# RMP_-_FBPS_MOBO_0_0_1.net
KiCad netlist of a schematic drawn in EAGLE
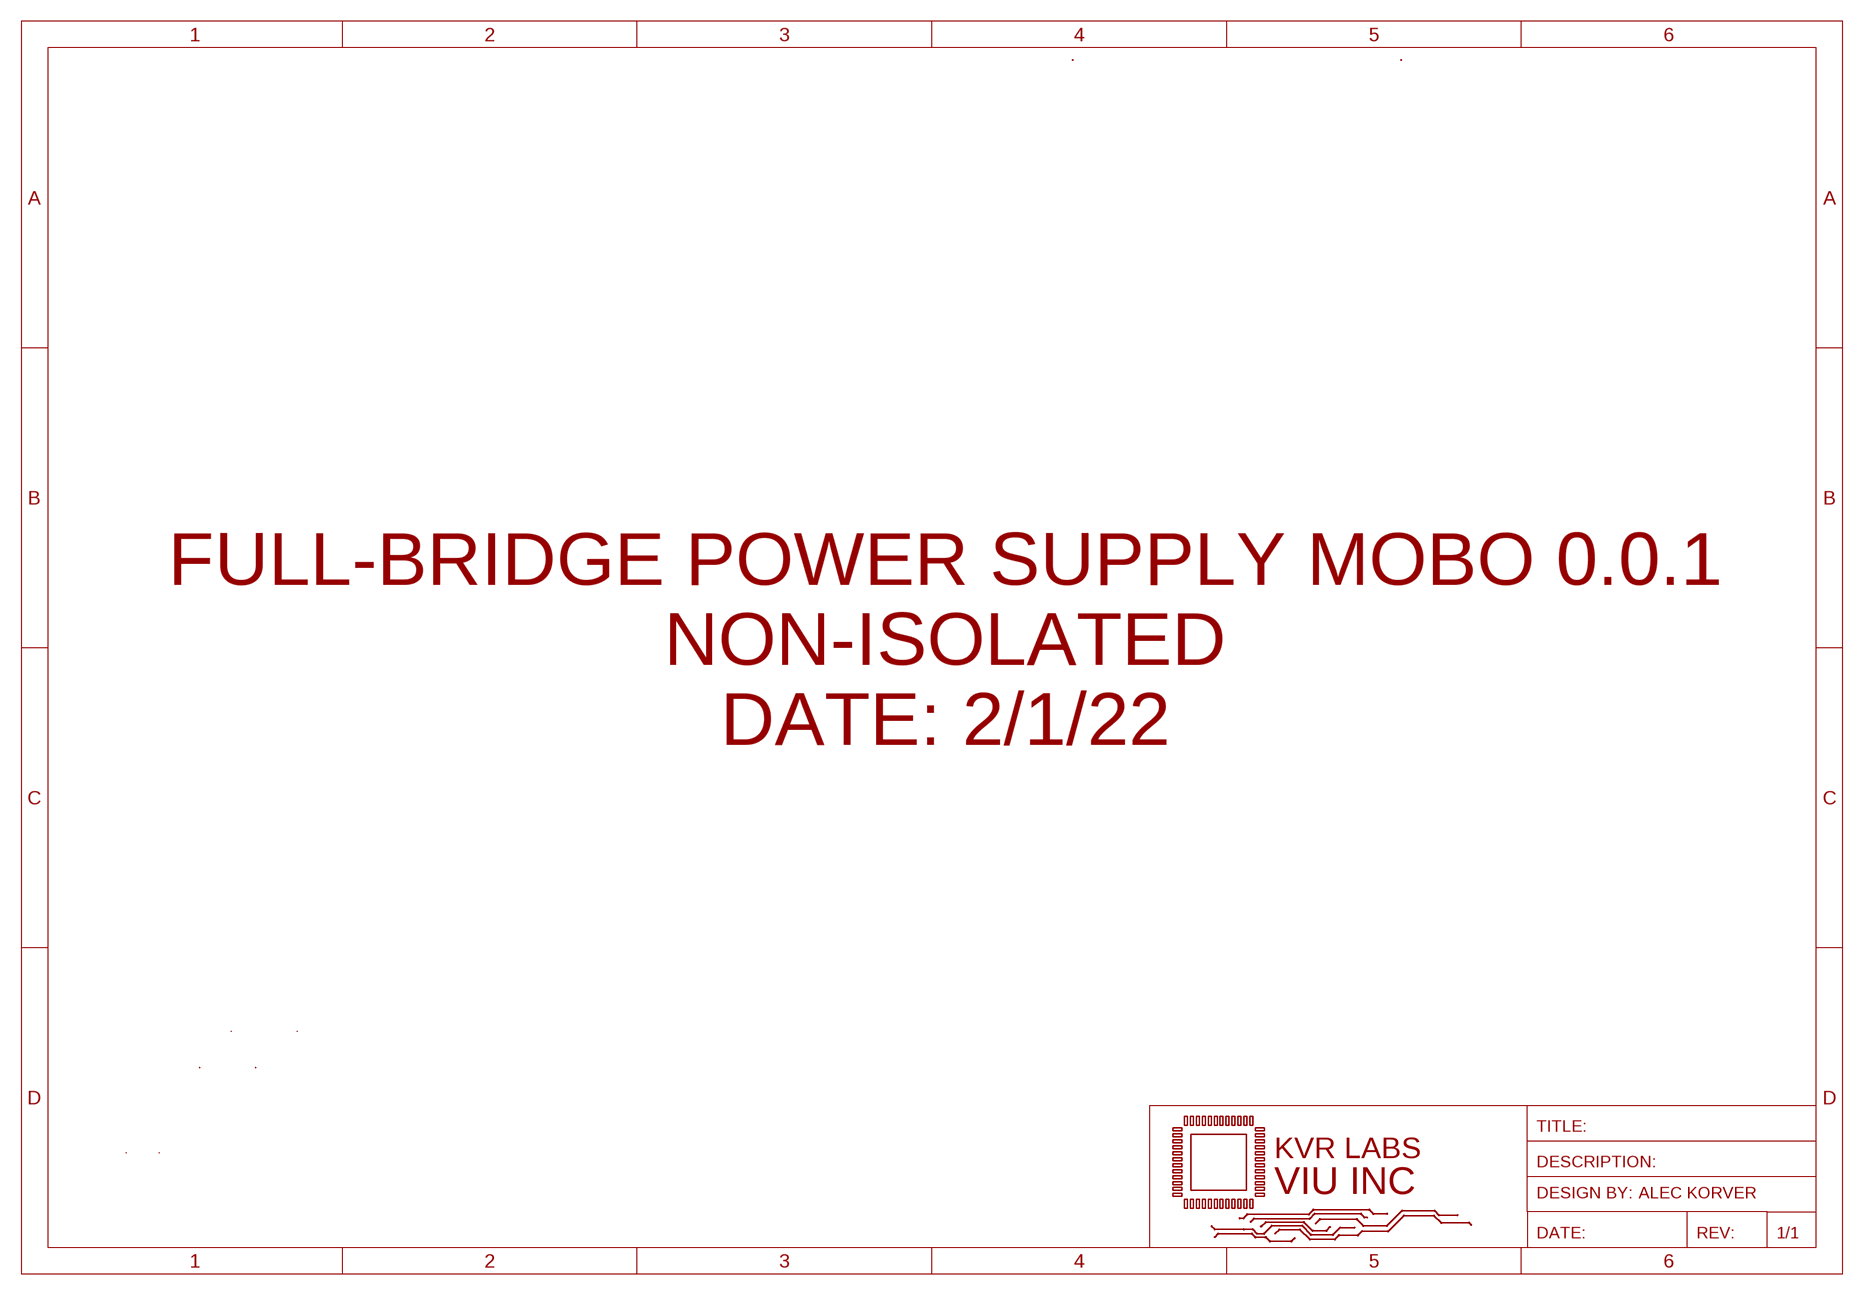
[diagram p0: schematic, sheet 1]
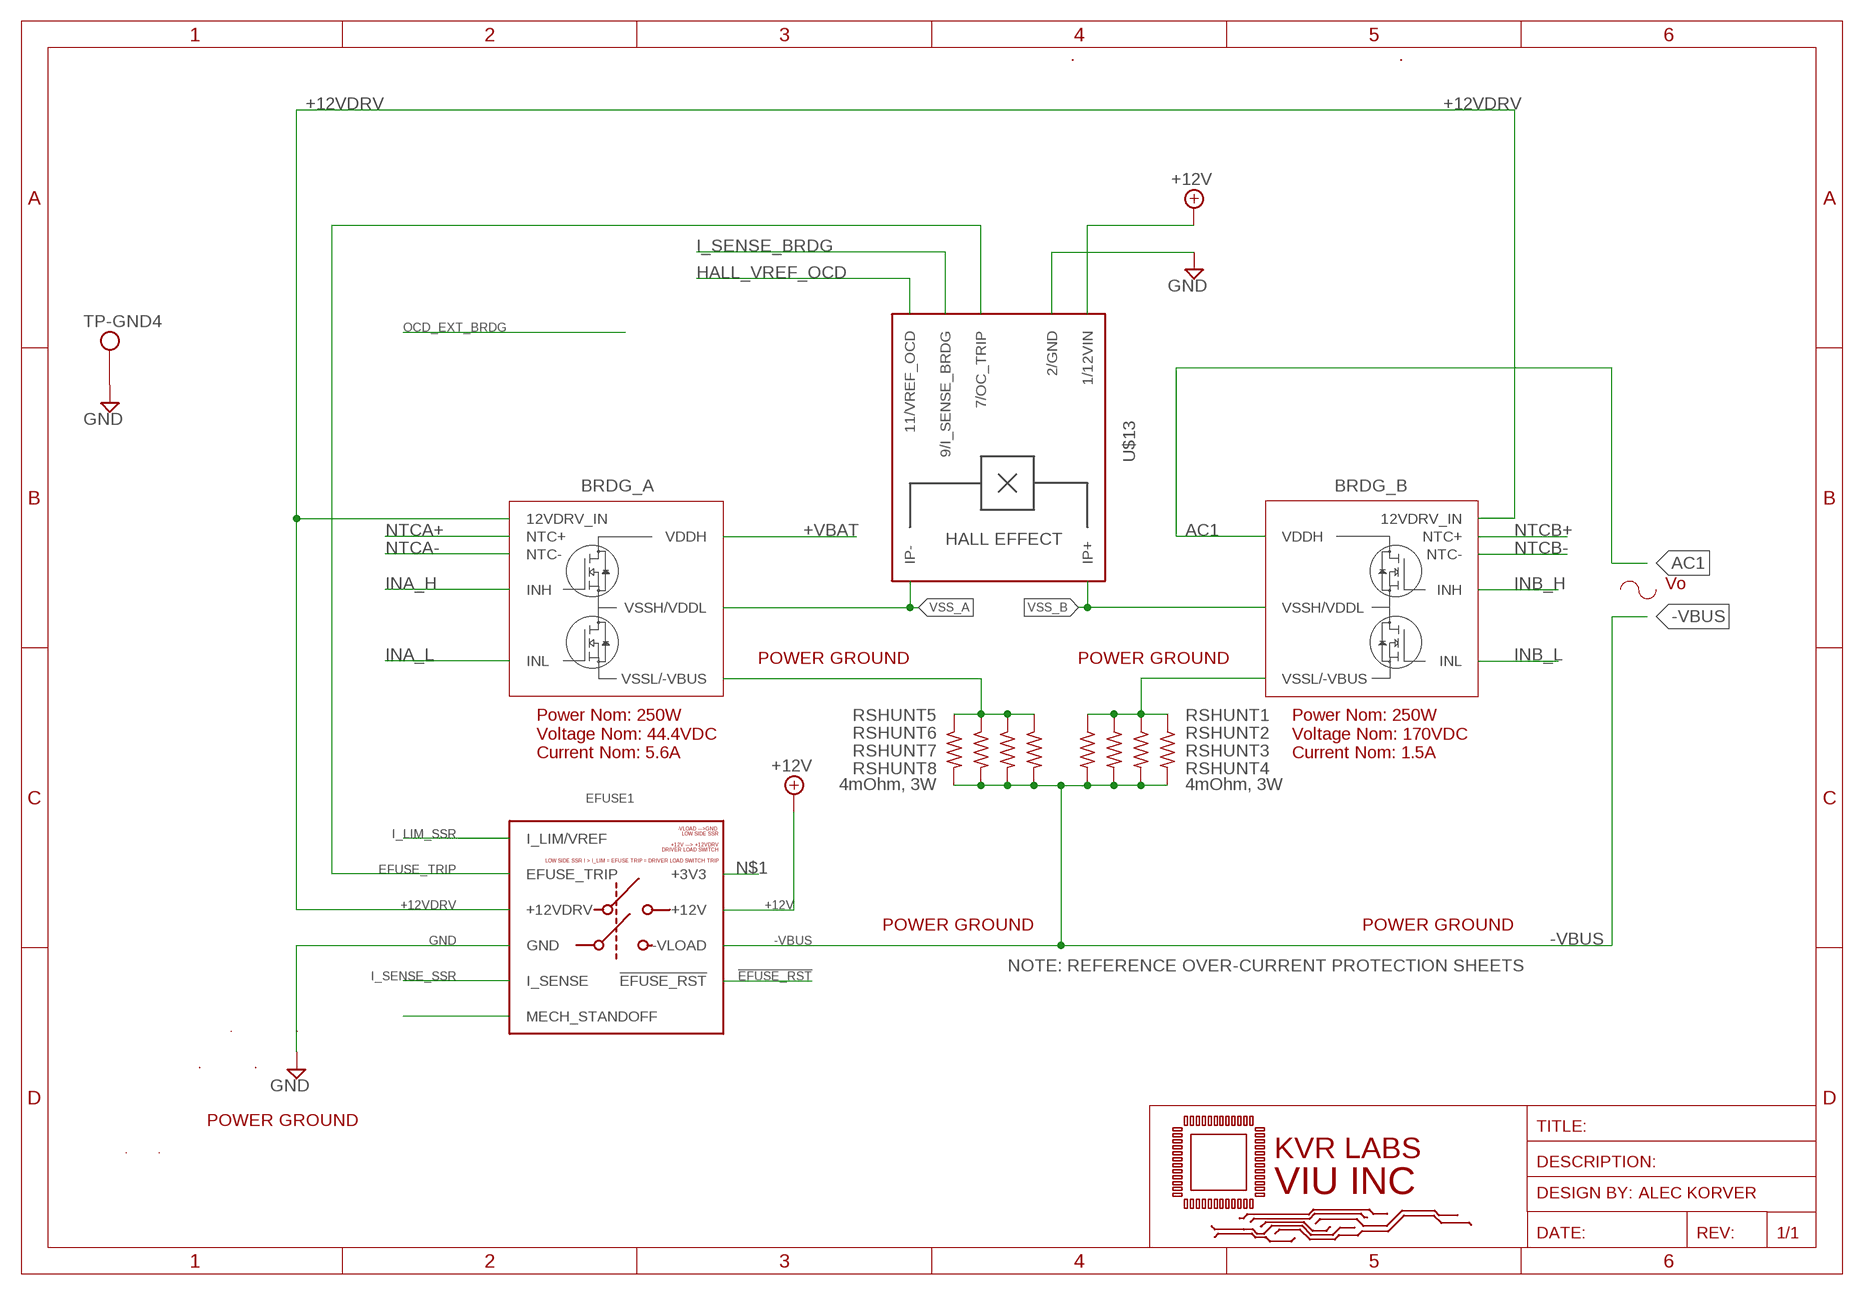
[diagram p1: schematic, sheet 2]
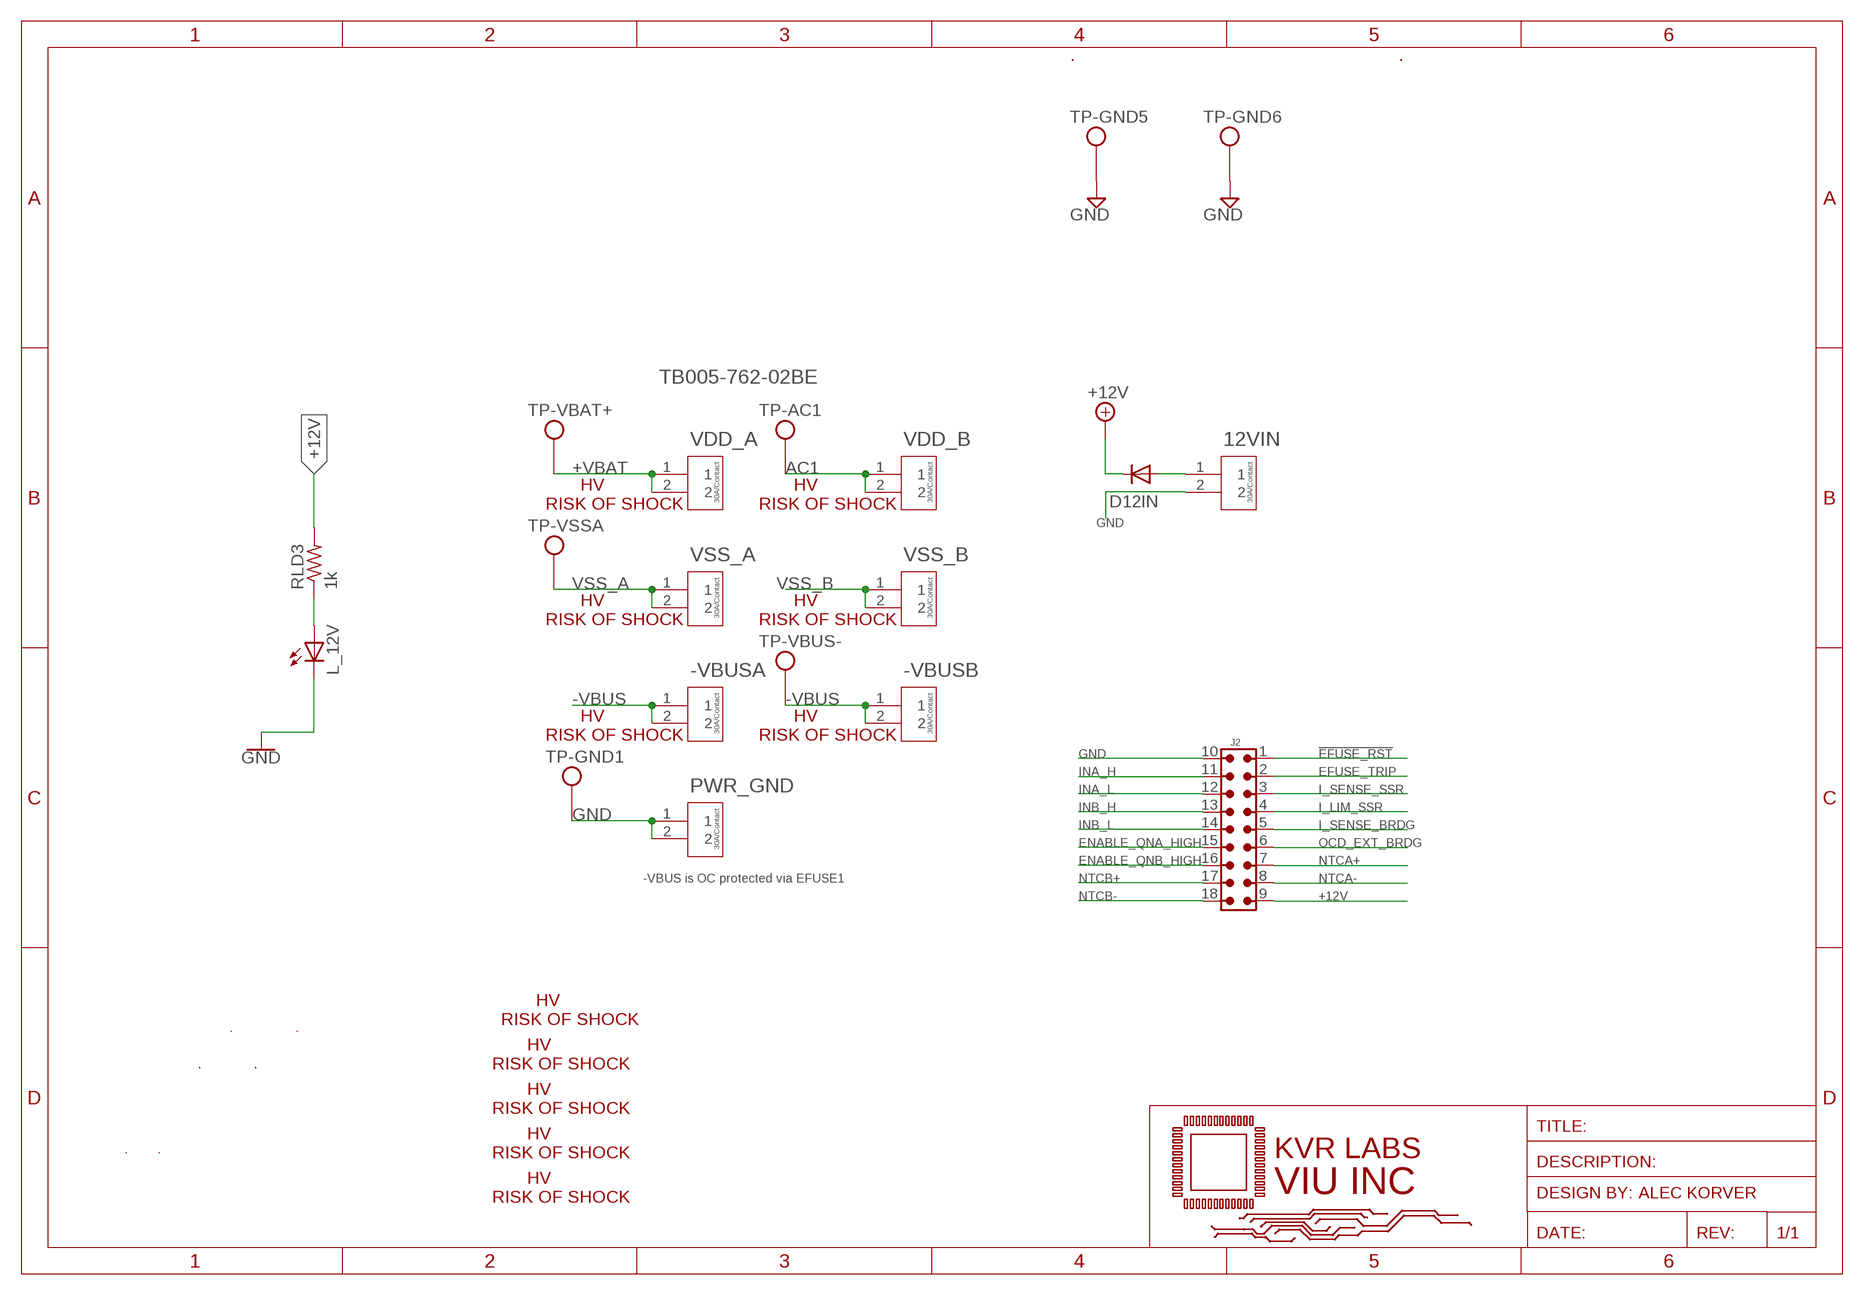
[diagram p2: schematic, sheet 3]
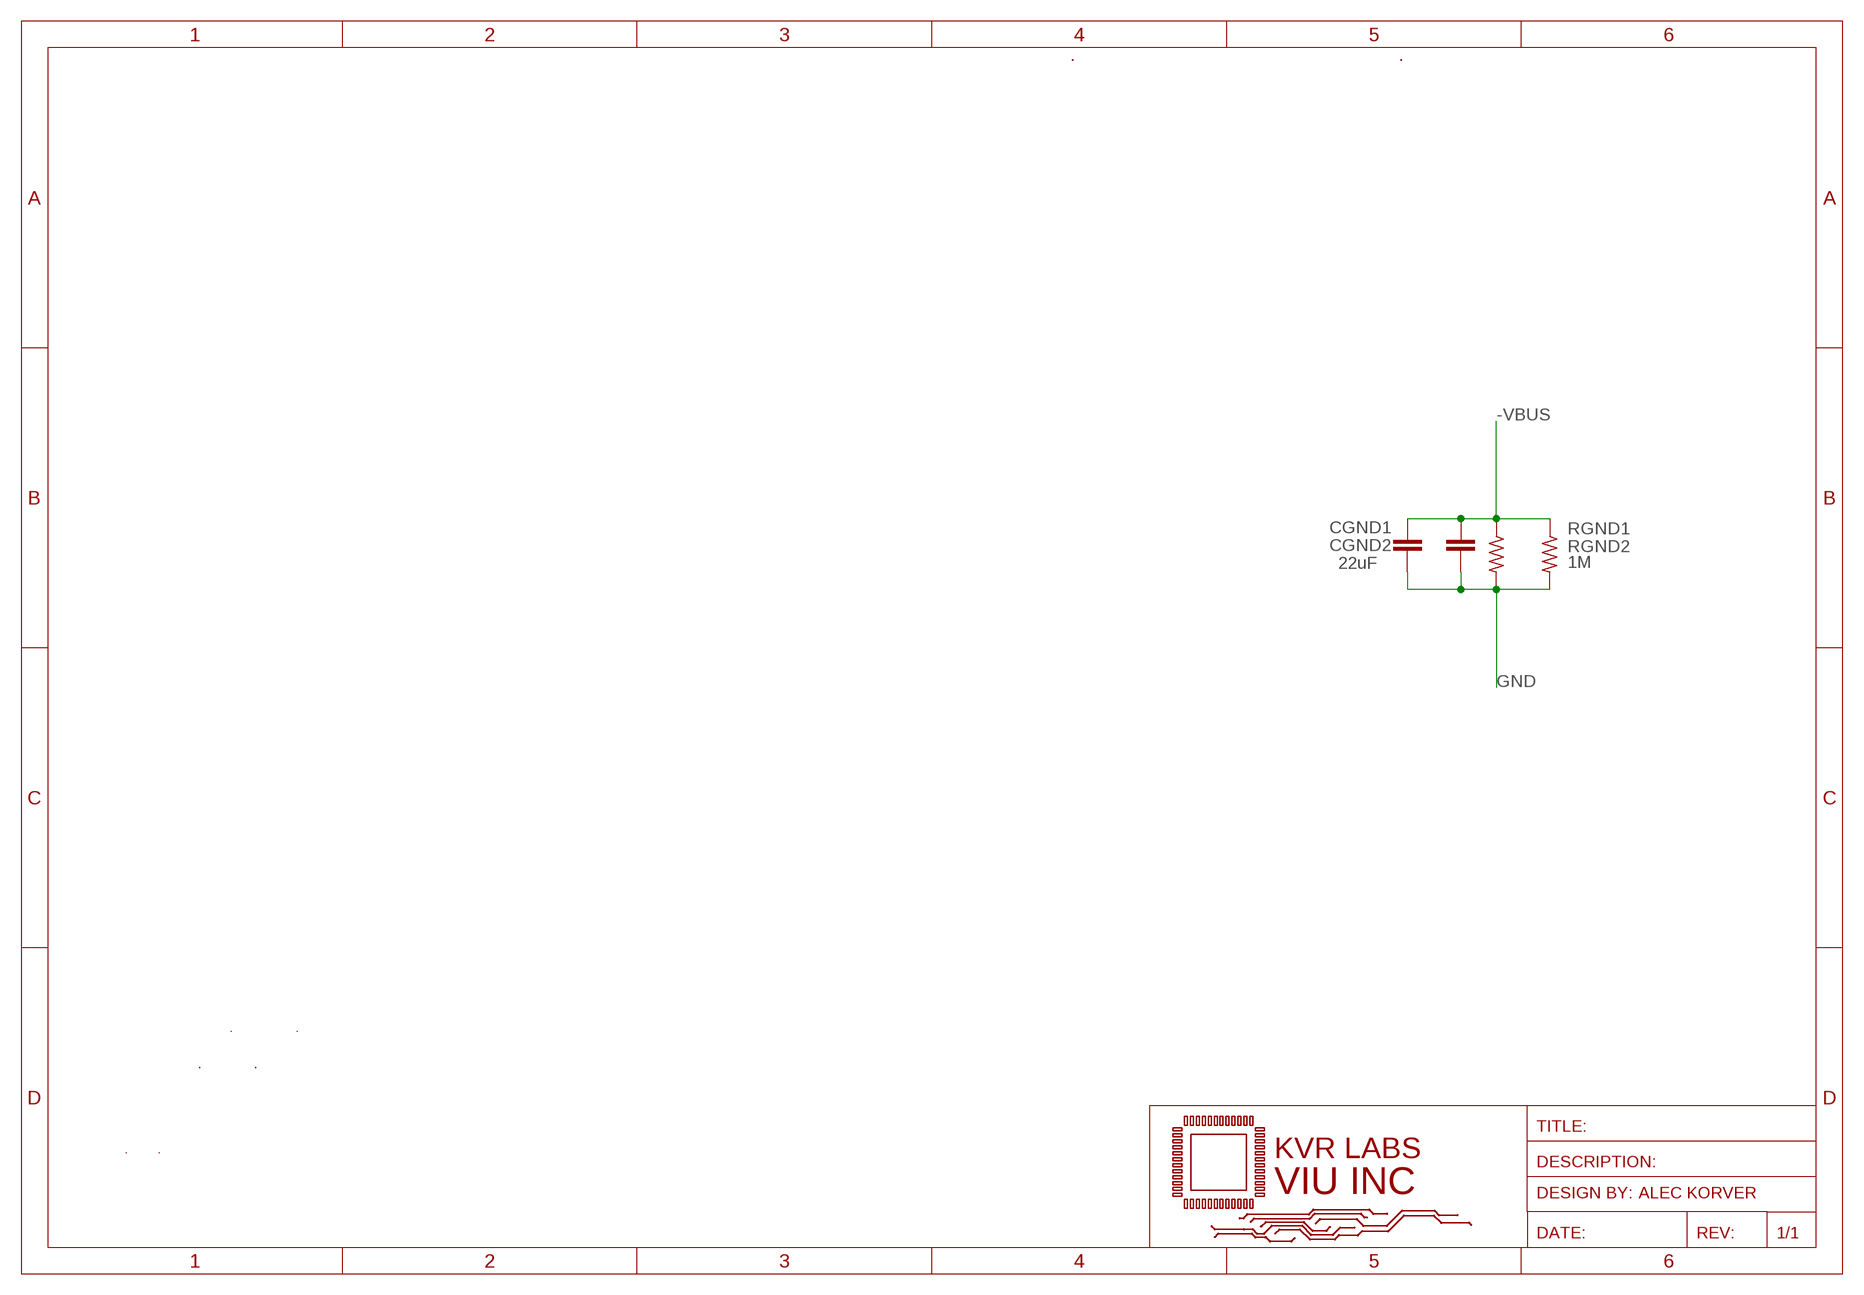
[diagram p3: schematic, sheet 4]

(export (version "E")
  (design (tool "Eeschema 10.0.6"))
  (components
    (comp (ref "BRDG_A")
      (value "1/2BRIDGE")
      (footprint "eagle-import:1_2BRIDGE")
      (fields (field (name "LCSC_PART") "DNP/CUSTOM"))
      (libsource (lib "eagle-import") (part "1/2BRIDGE"))
    )
    (comp (ref "BRDG_B")
      (value "1/2BRIDGE")
      (footprint "eagle-import:1_2BRIDGE")
      (fields (field (name "LCSC_PART") "DNP/CUSTOM"))
      (libsource (lib "eagle-import") (part "1/2BRIDGE"))
    )
    (comp (ref "EFUSE1")
      (value "EFUSE_2.0.0")
      (footprint "eagle-import:EFUSE_2.0.0")
      (fields (field (name "LCSC_PART") "DNP/CUSTOM"))
      (libsource (lib "eagle-import") (part "EFUSE_2.0.0"))
    )
    (comp (ref "RSHUNT1")
      (value "4mOhm, 3W")
      (footprint "eagle-import:R2512")
      (fields (field (name "LCSC_PART") "C728322"))
      (libsource (lib "eagle-import") (part "R-US_R2512"))
    )
    (comp (ref "RSHUNT2")
      (value "4mOhm, 3W")
      (footprint "eagle-import:R2512")
      (fields (field (name "LCSC_PART") "C728322"))
      (libsource (lib "eagle-import") (part "R-US_R2512"))
    )
    (comp (ref "RSHUNT3")
      (value "4mOhm, 3W")
      (footprint "eagle-import:R2512")
      (fields (field (name "LCSC_PART") "C728322"))
      (libsource (lib "eagle-import") (part "R-US_R2512"))
    )
    (comp (ref "RSHUNT4")
      (value "4mOhm, 3W")
      (footprint "eagle-import:R2512")
      (fields (field (name "LCSC_PART") "C728322"))
      (libsource (lib "eagle-import") (part "R-US_R2512"))
    )
    (comp (ref "RSHUNT5")
      (value "4mOhm, 3W")
      (footprint "eagle-import:R2512")
      (fields (field (name "LCSC_PART") "C728322"))
      (libsource (lib "eagle-import") (part "R-US_R2512"))
    )
    (comp (ref "RSHUNT6")
      (value "4mOhm, 3W")
      (footprint "eagle-import:R2512")
      (fields (field (name "LCSC_PART") "C728322"))
      (libsource (lib "eagle-import") (part "R-US_R2512"))
    )
    (comp (ref "RSHUNT7")
      (value "4mOhm, 3W")
      (footprint "eagle-import:R2512")
      (fields (field (name "LCSC_PART") "C728322"))
      (libsource (lib "eagle-import") (part "R-US_R2512"))
    )
    (comp (ref "RSHUNT8")
      (value "4mOhm, 3W")
      (footprint "eagle-import:R2512")
      (fields (field (name "LCSC_PART") "C728322"))
      (libsource (lib "eagle-import") (part "R-US_R2512"))
    )
    (comp (ref "TP-GND4")
      (value "THM_TESTPOINT_5000_SERIES")
      (footprint "eagle-import:THM-TESTPOINT")
      (fields (field (name "LCSC_PART") "DNP"))
      (libsource (lib "eagle-import") (part "THM_TESTPOINT_5000_SERIES"))
    )
    (comp (ref "U$13")
      (value "HALL_EFFECT_CURRENT_MONITOR")
      (footprint "eagle-import:HALL_CURRENT_MONITOR")
      (fields (field (name "LCSC_PART") "DNP/CUSTOM"))
      (libsource (lib "eagle-import") (part "HALL_EFFECT_CURRENT_MONITOR"))
    )
    (comp (ref "-VBUSA")
      (value "TB005-762-02BE")
      (footprint "eagle-import:TB005-762-02BE_CUD")
      (fields
        (field (name "LCSC_PART") "DNP")
        (field (name "COPYRIGHT") "Copyright (C) 2021 Ultra Librarian. All rights reserved.")
      )
      (libsource (lib "eagle-import") (part "TB005-762-02BE"))
    )
    (comp (ref "-VBUSB")
      (value "TB005-762-02BE")
      (footprint "eagle-import:TB005-762-02BE_CUD")
      (fields
        (field (name "LCSC_PART") "DNP")
        (field (name "COPYRIGHT") "Copyright (C) 2021 Ultra Librarian. All rights reserved.")
      )
      (libsource (lib "eagle-import") (part "TB005-762-02BE"))
    )
    (comp (ref "12VIN")
      (value "TB005-762-02BE")
      (footprint "eagle-import:TB005-762-02BE_CUD")
      (fields
        (field (name "LCSC_PART") "DNP")
        (field (name "COPYRIGHT") "Copyright (C) 2021 Ultra Librarian. All rights reserved.")
      )
      (libsource (lib "eagle-import") (part "TB005-762-02BE"))
    )
    (comp (ref "D12IN")
      (value "DIODESMA")
      (footprint "eagle-import:SMADIODE")
      (fields (field (name "LCSC_PART") "C110531"))
      (libsource (lib "eagle-import") (part "DIODESMA"))
    )
    (comp (ref "J2")
      (value "6620XX21022_66201821022")
      (footprint "eagle-import:66201821022")
      (fields (field (name "LCSC_PART") "DNP"))
      (libsource (lib "eagle-import") (part "6620XX21022_66201821022"))
    )
    (comp (ref "L_12V")
      (value "LEDCHIPLED_1206")
      (footprint "eagle-import:CHIPLED_1206")
      (fields (field (name "LCSC_PART") "C434439"))
      (libsource (lib "eagle-import") (part "LEDCHIPLED_1206"))
    )
    (comp (ref "PWR_GND")
      (value "TB005-762-02BE")
      (footprint "eagle-import:TB005-762-02BE_CUD")
      (fields
        (field (name "LCSC_PART") "DNP")
        (field (name "COPYRIGHT") "Copyright (C) 2021 Ultra Librarian. All rights reserved.")
      )
      (libsource (lib "eagle-import") (part "TB005-762-02BE"))
    )
    (comp (ref "RLD3")
      (value "1k")
      (footprint "eagle-import:R1206")
      (fields (field (name "LCSC_PART") "C115421"))
      (libsource (lib "eagle-import") (part "R-US_R1206"))
    )
    (comp (ref "TP-AC1")
      (value "THM_TESTPOINT_5000_SERIES")
      (footprint "eagle-import:THM-TESTPOINT")
      (fields (field (name "LCSC_PART") "DNP"))
      (libsource (lib "eagle-import") (part "THM_TESTPOINT_5000_SERIES"))
    )
    (comp (ref "TP-GND1")
      (value "THM_TESTPOINT_5000_SERIES")
      (footprint "eagle-import:THM-TESTPOINT")
      (fields (field (name "LCSC_PART") "DNP"))
      (libsource (lib "eagle-import") (part "THM_TESTPOINT_5000_SERIES"))
    )
    (comp (ref "TP-GND5")
      (value "THM_TESTPOINT_5000_SERIES")
      (footprint "eagle-import:THM-TESTPOINT")
      (fields (field (name "LCSC_PART") "DNP"))
      (libsource (lib "eagle-import") (part "THM_TESTPOINT_5000_SERIES"))
    )
    (comp (ref "TP-GND6")
      (value "THM_TESTPOINT_5000_SERIES")
      (footprint "eagle-import:THM-TESTPOINT")
      (fields (field (name "LCSC_PART") "DNP"))
      (libsource (lib "eagle-import") (part "THM_TESTPOINT_5000_SERIES"))
    )
    (comp (ref "TP-VBAT+")
      (value "THM_TESTPOINT_5000_SERIES")
      (footprint "eagle-import:THM-TESTPOINT")
      (fields (field (name "LCSC_PART") "DNP"))
      (libsource (lib "eagle-import") (part "THM_TESTPOINT_5000_SERIES"))
    )
    (comp (ref "TP-VBUS-")
      (value "THM_TESTPOINT_5000_SERIES")
      (footprint "eagle-import:THM-TESTPOINT")
      (fields (field (name "LCSC_PART") "DNP"))
      (libsource (lib "eagle-import") (part "THM_TESTPOINT_5000_SERIES"))
    )
    (comp (ref "TP-VSSA")
      (value "THM_TESTPOINT_5000_SERIES")
      (footprint "eagle-import:THM-TESTPOINT")
      (fields (field (name "LCSC_PART") "DNP"))
      (libsource (lib "eagle-import") (part "THM_TESTPOINT_5000_SERIES"))
    )
    (comp (ref "U$1")
      (value "ELECTRIC_SHOCK")
      (footprint "eagle-import:ELECTRIC_SHOCK")
      (fields (field (name "LCSC_PART") "DNP"))
      (libsource (lib "eagle-import") (part "ELECTRIC_SHOCK"))
    )
    (comp (ref "U$2")
      (value "ELECTRIC_SHOCK")
      (footprint "eagle-import:ELECTRIC_SHOCK")
      (fields (field (name "LCSC_PART") "DNP"))
      (libsource (lib "eagle-import") (part "ELECTRIC_SHOCK"))
    )
    (comp (ref "U$3")
      (value "ELECTRIC_SHOCK")
      (footprint "eagle-import:ELECTRIC_SHOCK")
      (fields (field (name "LCSC_PART") "DNP"))
      (libsource (lib "eagle-import") (part "ELECTRIC_SHOCK"))
    )
    (comp (ref "U$4")
      (value "ELECTRIC_SHOCK")
      (footprint "eagle-import:ELECTRIC_SHOCK")
      (fields (field (name "LCSC_PART") "DNP"))
      (libsource (lib "eagle-import") (part "ELECTRIC_SHOCK"))
    )
    (comp (ref "U$5")
      (value "ELECTRIC_SHOCK")
      (footprint "eagle-import:ELECTRIC_SHOCK")
      (fields (field (name "LCSC_PART") "DNP"))
      (libsource (lib "eagle-import") (part "ELECTRIC_SHOCK"))
    )
    (comp (ref "U$6")
      (value "ELECTRIC_SHOCK")
      (footprint "eagle-import:ELECTRIC_SHOCK")
      (fields (field (name "LCSC_PART") "DNP"))
      (libsource (lib "eagle-import") (part "ELECTRIC_SHOCK"))
    )
    (comp (ref "U$7")
      (value "ELECTRIC_SHOCK")
      (footprint "eagle-import:ELECTRIC_SHOCK")
      (fields (field (name "LCSC_PART") "DNP"))
      (libsource (lib "eagle-import") (part "ELECTRIC_SHOCK"))
    )
    (comp (ref "U$8")
      (value "ELECTRIC_SHOCK")
      (footprint "eagle-import:ELECTRIC_SHOCK")
      (fields (field (name "LCSC_PART") "DNP"))
      (libsource (lib "eagle-import") (part "ELECTRIC_SHOCK"))
    )
    (comp (ref "U$9")
      (value "ELECTRIC_SHOCK")
      (footprint "eagle-import:ELECTRIC_SHOCK")
      (fields (field (name "LCSC_PART") "DNP"))
      (libsource (lib "eagle-import") (part "ELECTRIC_SHOCK"))
    )
    (comp (ref "U$10")
      (value "ELECTRIC_SHOCK")
      (footprint "eagle-import:ELECTRIC_SHOCK")
      (fields (field (name "LCSC_PART") "DNP"))
      (libsource (lib "eagle-import") (part "ELECTRIC_SHOCK"))
    )
    (comp (ref "U$11")
      (value "ELECTRIC_SHOCK")
      (footprint "eagle-import:ELECTRIC_SHOCK")
      (fields (field (name "LCSC_PART") "DNP"))
      (libsource (lib "eagle-import") (part "ELECTRIC_SHOCK"))
    )
    (comp (ref "VDD_A")
      (value "TB005-762-02BE")
      (footprint "eagle-import:TB005-762-02BE_CUD")
      (fields
        (field (name "LCSC_PART") "DNP")
        (field (name "COPYRIGHT") "Copyright (C) 2021 Ultra Librarian. All rights reserved.")
      )
      (libsource (lib "eagle-import") (part "TB005-762-02BE"))
    )
    (comp (ref "VDD_B")
      (value "TB005-762-02BE")
      (footprint "eagle-import:TB005-762-02BE_CUD")
      (fields
        (field (name "LCSC_PART") "DNP")
        (field (name "COPYRIGHT") "Copyright (C) 2021 Ultra Librarian. All rights reserved.")
      )
      (libsource (lib "eagle-import") (part "TB005-762-02BE"))
    )
    (comp (ref "VSS_A")
      (value "TB005-762-02BE")
      (footprint "eagle-import:TB005-762-02BE_CUD")
      (fields
        (field (name "LCSC_PART") "DNP")
        (field (name "COPYRIGHT") "Copyright (C) 2021 Ultra Librarian. All rights reserved.")
      )
      (libsource (lib "eagle-import") (part "TB005-762-02BE"))
    )
    (comp (ref "VSS_B")
      (value "TB005-762-02BE")
      (footprint "eagle-import:TB005-762-02BE_CUD")
      (fields
        (field (name "LCSC_PART") "DNP")
        (field (name "COPYRIGHT") "Copyright (C) 2021 Ultra Librarian. All rights reserved.")
      )
      (libsource (lib "eagle-import") (part "TB005-762-02BE"))
    )
    (comp (ref "CGND1")
      (value "22uF")
      (footprint "eagle-import:C1206")
      (fields (field (name "LCSC_PART") "DNP/C77091"))
      (libsource (lib "eagle-import") (part "C-EUC1206"))
    )
    (comp (ref "CGND2")
      (value "22uF")
      (footprint "eagle-import:C1206")
      (fields (field (name "LCSC_PART") "DNP/C77091"))
      (libsource (lib "eagle-import") (part "C-EUC1206"))
    )
    (comp (ref "RGND1")
      (value "1M")
      (footprint "eagle-import:R1206")
      (fields (field (name "LCSC_PART") "DNP/C26124"))
      (libsource (lib "eagle-import") (part "R-US_R1206"))
    )
    (comp (ref "RGND2")
      (value "1M")
      (footprint "eagle-import:R1206")
      (fields (field (name "LCSC_PART") "DNP/C26124"))
      (libsource (lib "eagle-import") (part "R-US_R1206"))
    )
  )
  (nets
    (net (code "1") (name "+12V") (class "Default")
      (node (ref "D12IN") (pin "C") (pinfunction "C_C") (pintype "passive"))
      (node (ref "EFUSE1") (pin "11/12VIN") (pinfunction "+12V_11/12VIN") (pintype "input"))
      (node (ref "J2") (pin "9") (pinfunction "9_9") (pintype "passive"))
      (node (ref "RLD3") (pin "2") (pinfunction "2_2") (pintype "passive"))
      (node (ref "U$13") (pin "1/+12VIN") (pinfunction "1/12VIN_1/+12VIN") (pintype "bidirectional"))
    )
    (net (code "2") (name "+12VDRV") (class "Default")
      (node (ref "BRDG_A") (pin "11/+12DRVR") (pinfunction "12VDRV_IN_11/+12DRVR") (pintype "bidirectional"))
      (node (ref "BRDG_B") (pin "11/+12DRVR") (pinfunction "12VDRV_IN_11/+12DRVR") (pintype "bidirectional"))
      (node (ref "EFUSE1") (pin "12/12VDRV") (pinfunction "+12VDRV_12/12VDRV") (pintype "output"))
    )
    (net (code "3") (name "+VBAT") (class "Default")
      (node (ref "BRDG_A") (pin "1/VDDA") (pinfunction "VDDH_1/VDDA") (pintype "bidirectional"))
      (node (ref "BRDG_A") (pin "2/VDDA") (pinfunction "VDDH_2/VDDA") (pintype "bidirectional"))
      (node (ref "BRDG_A") (pin "3/VDDA") (pinfunction "VDDH_3/VDDA") (pintype "bidirectional"))
      (node (ref "BRDG_A") (pin "4/VDDA") (pinfunction "VDDH_4/VDDA") (pintype "bidirectional"))
      (node (ref "TP-VBAT+") (pin "P1") (pinfunction "P$1_P1") (pintype "bidirectional"))
      (node (ref "VDD_A") (pin "1") (pinfunction "1_1") (pintype "passive"))
      (node (ref "VDD_A") (pin "2") (pinfunction "2_2") (pintype "passive"))
    )
    (net (code "4") (name "-VBUS") (class "Default")
      (node (ref "-VBUSA") (pin "1") (pinfunction "1_1") (pintype "passive"))
      (node (ref "-VBUSA") (pin "2") (pinfunction "2_2") (pintype "passive"))
      (node (ref "-VBUSB") (pin "1") (pinfunction "1_1") (pintype "passive"))
      (node (ref "-VBUSB") (pin "2") (pinfunction "2_2") (pintype "passive"))
      (node (ref "CGND1") (pin "1") (pinfunction "1_1") (pintype "passive"))
      (node (ref "CGND2") (pin "1") (pinfunction "1_1") (pintype "passive"))
      (node (ref "EFUSE1") (pin "1/-VLOAD") (pinfunction "-VLOAD_1/-VLOAD") (pintype "input"))
      (node (ref "EFUSE1") (pin "2/-VLOAD") (pinfunction "-VLOAD_2/-VLOAD") (pintype "input"))
      (node (ref "EFUSE1") (pin "3/-VLOAD") (pinfunction "-VLOAD_3/-VLOAD") (pintype "input"))
      (node (ref "EFUSE1") (pin "4/-VLOAD") (pinfunction "-VLOAD_4/-VLOAD") (pintype "input"))
      (node (ref "EFUSE1") (pin "5/-VLOAD") (pinfunction "-VLOAD_5/-VLOAD") (pintype "input"))
      (node (ref "EFUSE1") (pin "6/-VLOAD") (pinfunction "-VLOAD_6/-VLOAD") (pintype "input"))
      (node (ref "EFUSE1") (pin "7/-VLOAD") (pinfunction "-VLOAD_7/-VLOAD") (pintype "input"))
      (node (ref "EFUSE1") (pin "8/-VLOAD") (pinfunction "-VLOAD_8/-VLOAD") (pintype "input"))
      (node (ref "RGND1") (pin "1") (pinfunction "1_1") (pintype "passive"))
      (node (ref "RGND2") (pin "1") (pinfunction "1_1") (pintype "passive"))
      (node (ref "RSHUNT1") (pin "2") (pinfunction "2_2") (pintype "passive"))
      (node (ref "RSHUNT2") (pin "2") (pinfunction "2_2") (pintype "passive"))
      (node (ref "RSHUNT3") (pin "2") (pinfunction "2_2") (pintype "passive"))
      (node (ref "RSHUNT4") (pin "2") (pinfunction "2_2") (pintype "passive"))
      (node (ref "RSHUNT5") (pin "2") (pinfunction "2_2") (pintype "passive"))
      (node (ref "RSHUNT6") (pin "2") (pinfunction "2_2") (pintype "passive"))
      (node (ref "RSHUNT7") (pin "2") (pinfunction "2_2") (pintype "passive"))
      (node (ref "RSHUNT8") (pin "2") (pinfunction "2_2") (pintype "passive"))
      (node (ref "TP-VBUS-") (pin "P1") (pinfunction "P$1_P1") (pintype "bidirectional"))
    )
    (net (code "5") (name "AC1") (class "Default")
      (node (ref "BRDG_B") (pin "1/VDDA") (pinfunction "VDDH_1/VDDA") (pintype "bidirectional"))
      (node (ref "BRDG_B") (pin "2/VDDA") (pinfunction "VDDH_2/VDDA") (pintype "bidirectional"))
      (node (ref "BRDG_B") (pin "3/VDDA") (pinfunction "VDDH_3/VDDA") (pintype "bidirectional"))
      (node (ref "BRDG_B") (pin "4/VDDA") (pinfunction "VDDH_4/VDDA") (pintype "bidirectional"))
      (node (ref "TP-AC1") (pin "P1") (pinfunction "P$1_P1") (pintype "bidirectional"))
      (node (ref "VDD_B") (pin "1") (pinfunction "1_1") (pintype "passive"))
      (node (ref "VDD_B") (pin "2") (pinfunction "2_2") (pintype "passive"))
    )
    (net (code "6") (name "EFUSE_TRIP") (class "Default")
      (node (ref "EFUSE1") (pin "10/EFUSE_TRIP") (pinfunction "EFUSE_TRIP_10/EFUSE_TRIP") (pintype "output"))
      (node (ref "J2") (pin "2") (pinfunction "2_2") (pintype "passive"))
      (node (ref "U$13") (pin "7/EFUSE_TRIP") (pinfunction "7/OC_TRIP_7/EFUSE_TRIP") (pintype "bidirectional"))
    )
    (net (code "7") (name "ENABLE_QNA_HIGH") (class "Default")
      (node (ref "J2") (pin "15") (pinfunction "15_15") (pintype "passive"))
    )
    (net (code "8") (name "ENABLE_QNB_HIGH") (class "Default")
      (node (ref "J2") (pin "16") (pinfunction "16_16") (pintype "passive"))
    )
    (net (code "9") (name "GND") (class "Default")
      (node (ref "12VIN") (pin "2") (pinfunction "2_2") (pintype "passive"))
      (node (ref "CGND1") (pin "2") (pinfunction "2_2") (pintype "passive"))
      (node (ref "CGND2") (pin "2") (pinfunction "2_2") (pintype "passive"))
      (node (ref "EFUSE1") (pin "1/GND") (pinfunction "GND_1/GND") (pintype "output"))
      (node (ref "EFUSE1") (pin "2/GND") (pinfunction "GND_2/GND") (pintype "output"))
      (node (ref "EFUSE1") (pin "3/GND") (pinfunction "GND_3/GND") (pintype "output"))
      (node (ref "EFUSE1") (pin "4/GND") (pinfunction "GND_4/GND") (pintype "output"))
      (node (ref "EFUSE1") (pin "5/GND") (pinfunction "GND_5/GND") (pintype "output"))
      (node (ref "EFUSE1") (pin "6/GND") (pinfunction "GND_6/GND") (pintype "output"))
      (node (ref "EFUSE1") (pin "7/GND") (pinfunction "GND_7/GND") (pintype "output"))
      (node (ref "EFUSE1") (pin "8/GND") (pinfunction "GND_8/GND") (pintype "output"))
      (node (ref "EFUSE1") (pin "9/GND") (pinfunction "GND_9/GND") (pintype "output"))
      (node (ref "J2") (pin "10") (pinfunction "10_10") (pintype "passive"))
      (node (ref "L_12V") (pin "C") (pinfunction "C_C") (pintype "passive"))
      (node (ref "PWR_GND") (pin "1") (pinfunction "1_1") (pintype "passive"))
      (node (ref "PWR_GND") (pin "2") (pinfunction "2_2") (pintype "passive"))
      (node (ref "RGND1") (pin "2") (pinfunction "2_2") (pintype "passive"))
      (node (ref "RGND2") (pin "2") (pinfunction "2_2") (pintype "passive"))
      (node (ref "TP-GND1") (pin "P1") (pinfunction "P$1_P1") (pintype "bidirectional"))
      (node (ref "TP-GND4") (pin "P1") (pinfunction "P$1_P1") (pintype "bidirectional"))
      (node (ref "TP-GND5") (pin "P1") (pinfunction "P$1_P1") (pintype "bidirectional"))
      (node (ref "TP-GND6") (pin "P1") (pinfunction "P$1_P1") (pintype "bidirectional"))
      (node (ref "U$13") (pin "2/GND") (pinfunction "2/GND_2/GND") (pintype "bidirectional"))
      (node (ref "U$13") (pin "3/GND") (pinfunction "2/GND_3/GND") (pintype "bidirectional"))
    )
    (net (code "10") (name "HALL_VREF_OCD") (class "Default")
      (node (ref "U$13") (pin "11/VREF_OCD") (pinfunction "11/VREF_OCD_11/VREF_OCD") (pintype "bidirectional"))
    )
    (net (code "11") (name "INA_H") (class "Default")
      (node (ref "BRDG_A") (pin "10/IN_H") (pinfunction "INH_10/IN_H") (pintype "bidirectional"))
      (node (ref "J2") (pin "11") (pinfunction "11_11") (pintype "passive"))
    )
    (net (code "12") (name "INA_L") (class "Default")
      (node (ref "BRDG_A") (pin "9/IN_L") (pinfunction "INL_9/IN_L") (pintype "bidirectional"))
      (node (ref "J2") (pin "12") (pinfunction "12_12") (pintype "passive"))
    )
    (net (code "13") (name "INB_H") (class "Default")
      (node (ref "BRDG_B") (pin "10/IN_H") (pinfunction "INH_10/IN_H") (pintype "bidirectional"))
      (node (ref "J2") (pin "13") (pinfunction "13_13") (pintype "passive"))
    )
    (net (code "14") (name "INB_L") (class "Default")
      (node (ref "BRDG_B") (pin "9/IN_L") (pinfunction "INL_9/IN_L") (pintype "bidirectional"))
      (node (ref "J2") (pin "14") (pinfunction "14_14") (pintype "passive"))
    )
    (net (code "15") (name "I_LIM_SSR") (class "Default")
      (node (ref "EFUSE1") (pin "11/VREF") (pinfunction "I_LIM/VREF_11/VREF") (pintype "output"))
      (node (ref "J2") (pin "4") (pinfunction "4_4") (pintype "passive"))
    )
    (net (code "16") (name "I_SENSE_BRDG") (class "Default")
      (node (ref "J2") (pin "5") (pinfunction "5_5") (pintype "passive"))
      (node (ref "U$13") (pin "9/I_SENSE_BRDG") (pinfunction "9/I_SENSE_BRDG_9/I_SENSE_BRDG") (pintype "bidirectional"))
    )
    (net (code "17") (name "I_SENSE_SSR") (class "Default")
      (node (ref "EFUSE1") (pin "9/-VLOAD_SW") (pinfunction "I_SENSE_9/-VLOAD_SW") (pintype "output"))
      (node (ref "J2") (pin "3") (pinfunction "3_3") (pintype "passive"))
    )
    (net (code "18") (name "N$1") (class "Default")
      (node (ref "EFUSE1") (pin "10/+3V3") (pinfunction "+3V3_10/+3V3") (pintype "power_in"))
    )
    (net (code "19") (name "NTCA+") (class "Default")
      (node (ref "BRDG_A") (pin "7/NTC+") (pinfunction "NTC+_7/NTC+") (pintype "bidirectional"))
      (node (ref "J2") (pin "7") (pinfunction "7_7") (pintype "passive"))
    )
    (net (code "20") (name "NTCA-") (class "Default")
      (node (ref "BRDG_A") (pin "8/NTC-") (pinfunction "NTC-_8/NTC-") (pintype "bidirectional"))
      (node (ref "J2") (pin "8") (pinfunction "8_8") (pintype "passive"))
    )
    (net (code "21") (name "NTCB+") (class "Default")
      (node (ref "BRDG_B") (pin "7/NTC+") (pinfunction "NTC+_7/NTC+") (pintype "bidirectional"))
      (node (ref "J2") (pin "17") (pinfunction "17_17") (pintype "passive"))
    )
    (net (code "22") (name "NTCB-") (class "Default")
      (node (ref "BRDG_B") (pin "8/NTC-") (pinfunction "NTC-_8/NTC-") (pintype "bidirectional"))
      (node (ref "J2") (pin "18") (pinfunction "18_18") (pintype "passive"))
    )
    (net (code "23") (name "Net-(12VIN-Pad1)") (class "Default")
      (node (ref "12VIN") (pin "1") (pinfunction "1_1") (pintype "passive"))
      (node (ref "D12IN") (pin "A") (pinfunction "A_A") (pintype "passive"))
    )
    (net (code "24") (name "Net-(BRDG_A-VSSL{slash}-VBUS-Pad10{slash}-VBUS)") (class "Default")
      (node (ref "BRDG_A") (pin "10/-VBUS") (pinfunction "VSSL/-VBUS_10/-VBUS") (pintype "bidirectional"))
      (node (ref "BRDG_A") (pin "11/-VBUS") (pinfunction "VSSL/-VBUS_11/-VBUS") (pintype "bidirectional"))
      (node (ref "BRDG_A") (pin "12/-VBUS") (pinfunction "VSSL/-VBUS_12/-VBUS") (pintype "bidirectional"))
      (node (ref "BRDG_A") (pin "9/-VBUS") (pinfunction "VSSL/-VBUS_9/-VBUS") (pintype "bidirectional"))
      (node (ref "RSHUNT5") (pin "1") (pinfunction "1_1") (pintype "passive"))
      (node (ref "RSHUNT6") (pin "1") (pinfunction "1_1") (pintype "passive"))
      (node (ref "RSHUNT7") (pin "1") (pinfunction "1_1") (pintype "passive"))
      (node (ref "RSHUNT8") (pin "1") (pinfunction "1_1") (pintype "passive"))
    )
    (net (code "25") (name "Net-(BRDG_B-VSSL{slash}-VBUS-Pad10{slash}-VBUS)") (class "Default")
      (node (ref "BRDG_B") (pin "10/-VBUS") (pinfunction "VSSL/-VBUS_10/-VBUS") (pintype "bidirectional"))
      (node (ref "BRDG_B") (pin "11/-VBUS") (pinfunction "VSSL/-VBUS_11/-VBUS") (pintype "bidirectional"))
      (node (ref "BRDG_B") (pin "12/-VBUS") (pinfunction "VSSL/-VBUS_12/-VBUS") (pintype "bidirectional"))
      (node (ref "BRDG_B") (pin "9/-VBUS") (pinfunction "VSSL/-VBUS_9/-VBUS") (pintype "bidirectional"))
      (node (ref "RSHUNT1") (pin "1") (pinfunction "1_1") (pintype "passive"))
      (node (ref "RSHUNT2") (pin "1") (pinfunction "1_1") (pintype "passive"))
      (node (ref "RSHUNT3") (pin "1") (pinfunction "1_1") (pintype "passive"))
      (node (ref "RSHUNT4") (pin "1") (pinfunction "1_1") (pintype "passive"))
    )
    (net (code "26") (name "Net-(EFUSE1-MECH_STANDOFF-PadS1)") (class "Default")
      (node (ref "EFUSE1") (pin "S1") (pinfunction "MECH_STANDOFF_S1") (pintype "bidirectional"))
      (node (ref "EFUSE1") (pin "S2") (pinfunction "MECH_STANDOFF_S2") (pintype "bidirectional"))
    )
    (net (code "27") (name "Net-(L_12V-PadA)") (class "Default")
      (node (ref "L_12V") (pin "A") (pinfunction "A_A") (pintype "passive"))
      (node (ref "RLD3") (pin "1") (pinfunction "1_1") (pintype "passive"))
    )
    (net (code "28") (name "OCD_EXT_BRDG") (class "Default")
      (node (ref "J2") (pin "6") (pinfunction "6_6") (pintype "passive"))
    )
    (net (code "29") (name "VSS_A") (class "Default")
      (node (ref "BRDG_A") (pin "1/VSSA") (pinfunction "VSSH/VDDL_1/VSSA") (pintype "bidirectional"))
      (node (ref "BRDG_A") (pin "2/VSSA") (pinfunction "VSSH/VDDL_2/VSSA") (pintype "bidirectional"))
      (node (ref "BRDG_A") (pin "3/VSSA") (pinfunction "VSSH/VDDL_3/VSSA") (pintype "bidirectional"))
      (node (ref "BRDG_A") (pin "4/VSSA") (pinfunction "VSSH/VDDL_4/VSSA") (pintype "bidirectional"))
      (node (ref "TP-VSSA") (pin "P1") (pinfunction "P$1_P1") (pintype "bidirectional"))
      (node (ref "U$13") (pin "10/IP-") (pinfunction "IP-_10/IP-") (pintype "bidirectional"))
      (node (ref "U$13") (pin "11/IP-") (pinfunction "IP-_11/IP-") (pintype "bidirectional"))
      (node (ref "U$13") (pin "12/IP-") (pinfunction "IP-_12/IP-") (pintype "bidirectional"))
      (node (ref "U$13") (pin "7/IP-") (pinfunction "IP-_7/IP-") (pintype "bidirectional"))
      (node (ref "U$13") (pin "8/IP-") (pinfunction "IP-_8/IP-") (pintype "bidirectional"))
      (node (ref "U$13") (pin "9/IP-") (pinfunction "IP-_9/IP-") (pintype "bidirectional"))
      (node (ref "VSS_A") (pin "1") (pinfunction "1_1") (pintype "passive"))
      (node (ref "VSS_A") (pin "2") (pinfunction "2_2") (pintype "passive"))
    )
    (net (code "30") (name "VSS_B") (class "Default")
      (node (ref "BRDG_B") (pin "1/VSSA") (pinfunction "VSSH/VDDL_1/VSSA") (pintype "bidirectional"))
      (node (ref "BRDG_B") (pin "2/VSSA") (pinfunction "VSSH/VDDL_2/VSSA") (pintype "bidirectional"))
      (node (ref "BRDG_B") (pin "3/VSSA") (pinfunction "VSSH/VDDL_3/VSSA") (pintype "bidirectional"))
      (node (ref "BRDG_B") (pin "4/VSSA") (pinfunction "VSSH/VDDL_4/VSSA") (pintype "bidirectional"))
      (node (ref "U$13") (pin "1/IP+") (pinfunction "IP+_1/IP+") (pintype "bidirectional"))
      (node (ref "U$13") (pin "2/IP+") (pinfunction "IP+_2/IP+") (pintype "bidirectional"))
      (node (ref "U$13") (pin "3/IP+") (pinfunction "IP+_3/IP+") (pintype "bidirectional"))
      (node (ref "U$13") (pin "4/IP+") (pinfunction "IP+_4/IP+") (pintype "bidirectional"))
      (node (ref "U$13") (pin "5/IP+") (pinfunction "IP+_5/IP+") (pintype "bidirectional"))
      (node (ref "U$13") (pin "6/IP+") (pinfunction "IP+_6/IP+") (pintype "bidirectional"))
      (node (ref "VSS_B") (pin "1") (pinfunction "1_1") (pintype "passive"))
      (node (ref "VSS_B") (pin "2") (pinfunction "2_2") (pintype "passive"))
    )
    (net (code "31") (name "~{EFUSE_RST}") (class "Default")
      (node (ref "EFUSE1") (pin "12/!EFUSE_RST") (pinfunction "~{EFUSE_RST}_12/!EFUSE_RST") (pintype "input"))
      (node (ref "J2") (pin "1") (pinfunction "1_1") (pintype "passive"))
    )
  )
)
